# debug_LED.net
KiCad netlist of a schematic drawn in Altium Designer
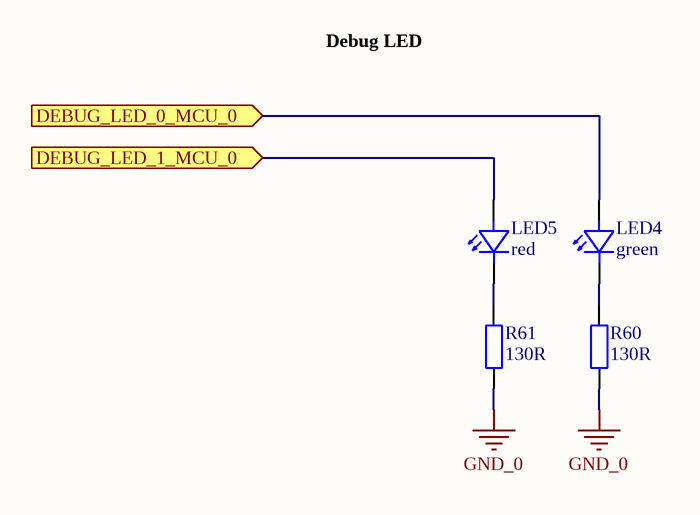
[diagram p0: debug_LED.SchDoc]

(export (version "E")
  (design (tool "Eeschema 10.0.6"))
  (components
    (comp (ref "LED4")
      (value "green")
      (footprint "LEDC1608X07N")
      (description "LED")
      (fields (field (name "PART NUMBER") "gen_LED_0603_green"))
      (libsource (lib "OE750") (part "D_LED"))
    )
    (comp (ref "LED5")
      (value "red")
      (footprint "LEDC1608X07N")
      (description "LED")
      (fields (field (name "PART NUMBER") "gen_LED_0603_red"))
      (libsource (lib "OE750") (part "D_LED"))
    )
    (comp (ref "R60")
      (value "130R")
      (footprint "0603R")
      (description "SMD Resistor 130R 0603")
      (fields (field (name "PART NUMBER") "gen_R_130R_0603") (field (name "TOLERANCE") "1%"))
      (libsource (lib "master-010106") (part "R"))
    )
    (comp (ref "R61")
      (value "130R")
      (footprint "0603R")
      (description "SMD Resistor 130R 0603")
      (fields (field (name "PART NUMBER") "gen_R_130R_0603") (field (name "TOLERANCE") "1%"))
      (libsource (lib "master-010106") (part "R"))
    )
  )
  (nets
    (net (code "1") (name "/DEBUG_LED_0_MCU_0") (class "Default")
      (node (ref "LED4") (pin "2") (pinfunction "A_2") (pintype "passive"))
    )
    (net (code "2") (name "/DEBUG_LED_1_MCU_0") (class "Default")
      (node (ref "LED5") (pin "2") (pinfunction "A_2") (pintype "passive"))
    )
    (net (code "3") (name "GND_0") (class "Default")
      (node (ref "R60") (pin "1") (pinfunction "1_1") (pintype "passive"))
      (node (ref "R61") (pin "1") (pinfunction "1_1") (pintype "passive"))
    )
    (net (code "4") (name "Net-(LED4-C)") (class "Default")
      (node (ref "LED4") (pin "1") (pinfunction "C_1") (pintype "passive"))
      (node (ref "R60") (pin "2") (pinfunction "2_2") (pintype "passive"))
    )
    (net (code "5") (name "Net-(LED5-C)") (class "Default")
      (node (ref "LED5") (pin "1") (pinfunction "C_1") (pintype "passive"))
      (node (ref "R61") (pin "2") (pinfunction "2_2") (pintype "passive"))
    )
  )
)
